# lm3410-sepic-led-driver-16mm-mk-4.net
KiCad netlist of a schematic drawn in EAGLE
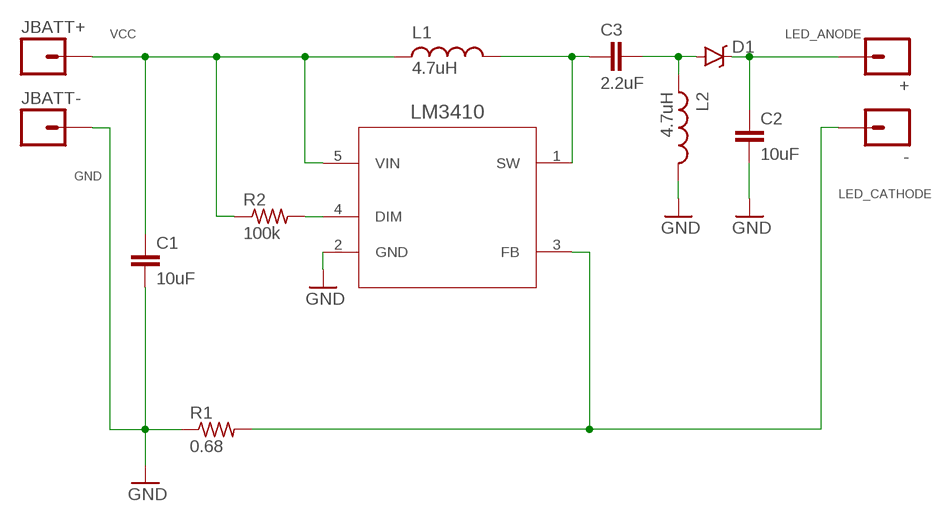
[diagram p0: schematic, sheet 1]

(export (version "E")
  (design (tool "Eeschema 10.0.6"))
  (components
    (comp (ref "+")
      (value "M01PTH-1.2MM")
      (footprint "eagle-import:1X01-1.2MM")
      (libsource (lib "eagle-import") (part "M01PTH-1.2MM"))
    )
    (comp (ref "-")
      (value "M01PTH-1.2MM-NS")
      (footprint "eagle-import:1X01-1.2MM-NS")
      (libsource (lib "eagle-import") (part "M01PTH-1.2MM-NS"))
    )
    (comp (ref "C1")
      (value "10uF")
      (footprint "eagle-import:C0603")
      (libsource (lib "eagle-import") (part "CAPACITOR-CERAMICC0603"))
    )
    (comp (ref "C2")
      (value "10uF")
      (footprint "eagle-import:C0603")
      (libsource (lib "eagle-import") (part "CAPACITOR-CERAMICC0603"))
    )
    (comp (ref "C3")
      (value "2.2uF")
      (footprint "eagle-import:C0805")
      (libsource (lib "eagle-import") (part "CAPACITOR-CERAMICC0805"))
    )
    (comp (ref "D1")
      (value "MBRA140")
      (footprint "eagle-import:SMA-DIODE")
      (libsource (lib "eagle-import") (part "DIODE-SCHOTTKYMBRA140"))
    )
    (comp (ref "JBATT+")
      (value "M01NOT-A-VIA-NOPE")
      (footprint "eagle-import:1X01_NOSILK_NOSTOP")
      (libsource (lib "eagle-import") (part "M01NOT-A-VIA-NOPE"))
    )
    (comp (ref "JBATT-")
      (value "M01NOT-A-VIA-NOPE")
      (footprint "eagle-import:1X01_NOSILK_NOSTOP")
      (libsource (lib "eagle-import") (part "M01NOT-A-VIA-NOPE"))
    )
    (comp (ref "L1")
      (value "4.7uH")
      (footprint "eagle-import:TAIYO-YUDEN-30XX")
      (libsource (lib "eagle-import") (part "INDUCTORTAIYO-YUDEN-30XX"))
    )
    (comp (ref "L2")
      (value "4.7uH")
      (footprint "eagle-import:TAIYO-YUDEN-30XX")
      (libsource (lib "eagle-import") (part "INDUCTORTAIYO-YUDEN-30XX"))
    )
    (comp (ref "LM3410")
      (value "LM3410XMF")
      (footprint "eagle-import:SOT95P285X120-5N")
      (libsource (lib "eagle-import") (part "LM3410XMF"))
    )
    (comp (ref "R1")
      (value "0.68")
      (footprint "eagle-import:R1206")
      (libsource (lib "eagle-import") (part "RESISTORR1206"))
    )
    (comp (ref "R2")
      (value "100k")
      (footprint "eagle-import:R0603")
      (libsource (lib "eagle-import") (part "RESISTORR0603"))
    )
  )
  (nets
    (net (code "1") (name "/LED_ANODE") (class "Default")
      (node (ref "+") (pin "P$1") (pinfunction "1_P$1") (pintype "passive"))
      (node (ref "C2") (pin "1") (pinfunction "1_1") (pintype "passive"))
      (node (ref "D1") (pin "C") (pinfunction "C_C") (pintype "passive"))
    )
    (net (code "2") (name "/LED_CATHODE") (class "Default")
      (node (ref "-") (pin "P$1") (pinfunction "1_P$1") (pintype "passive"))
      (node (ref "LM3410") (pin "3") (pinfunction "FB_3") (pintype "input"))
      (node (ref "R1") (pin "2") (pinfunction "2_2") (pintype "passive"))
    )
    (net (code "3") (name "/VCC") (class "Default")
      (node (ref "C1") (pin "1") (pinfunction "1_1") (pintype "passive"))
      (node (ref "JBATT+") (pin "P$1") (pinfunction "1_P$1") (pintype "passive"))
      (node (ref "L1") (pin "1") (pinfunction "1_1") (pintype "passive"))
      (node (ref "LM3410") (pin "5") (pinfunction "VIN_5") (pintype "power_in"))
      (node (ref "R2") (pin "1") (pinfunction "1_1") (pintype "passive"))
    )
    (net (code "4") (name "GND") (class "Default")
      (node (ref "C1") (pin "2") (pinfunction "2_2") (pintype "passive"))
      (node (ref "C2") (pin "2") (pinfunction "2_2") (pintype "passive"))
      (node (ref "JBATT-") (pin "P$1") (pinfunction "1_P$1") (pintype "passive"))
      (node (ref "L2") (pin "2") (pinfunction "2_2") (pintype "passive"))
      (node (ref "LM3410") (pin "2") (pinfunction "GND_2") (pintype "passive"))
      (node (ref "R1") (pin "1") (pinfunction "1_1") (pintype "passive"))
    )
    (net (code "5") (name "Net-(C3-Pad2)") (class "Default")
      (node (ref "C3") (pin "2") (pinfunction "2_2") (pintype "passive"))
      (node (ref "D1") (pin "A") (pinfunction "A_A") (pintype "passive"))
      (node (ref "L2") (pin "1") (pinfunction "1_1") (pintype "passive"))
    )
    (net (code "6") (name "Net-(LM3410-DIM)") (class "Default")
      (node (ref "LM3410") (pin "4") (pinfunction "DIM_4") (pintype "input"))
      (node (ref "R2") (pin "2") (pinfunction "2_2") (pintype "passive"))
    )
    (net (code "7") (name "Net-(LM3410-SW)") (class "Default")
      (node (ref "C3") (pin "1") (pinfunction "1_1") (pintype "passive"))
      (node (ref "L1") (pin "2") (pinfunction "2_2") (pintype "passive"))
      (node (ref "LM3410") (pin "1") (pinfunction "SW_1") (pintype "output"))
    )
  )
)
